# Sony_PS_Vita_USB-C.net
KiCad netlist of a schematic drawn in EAGLE
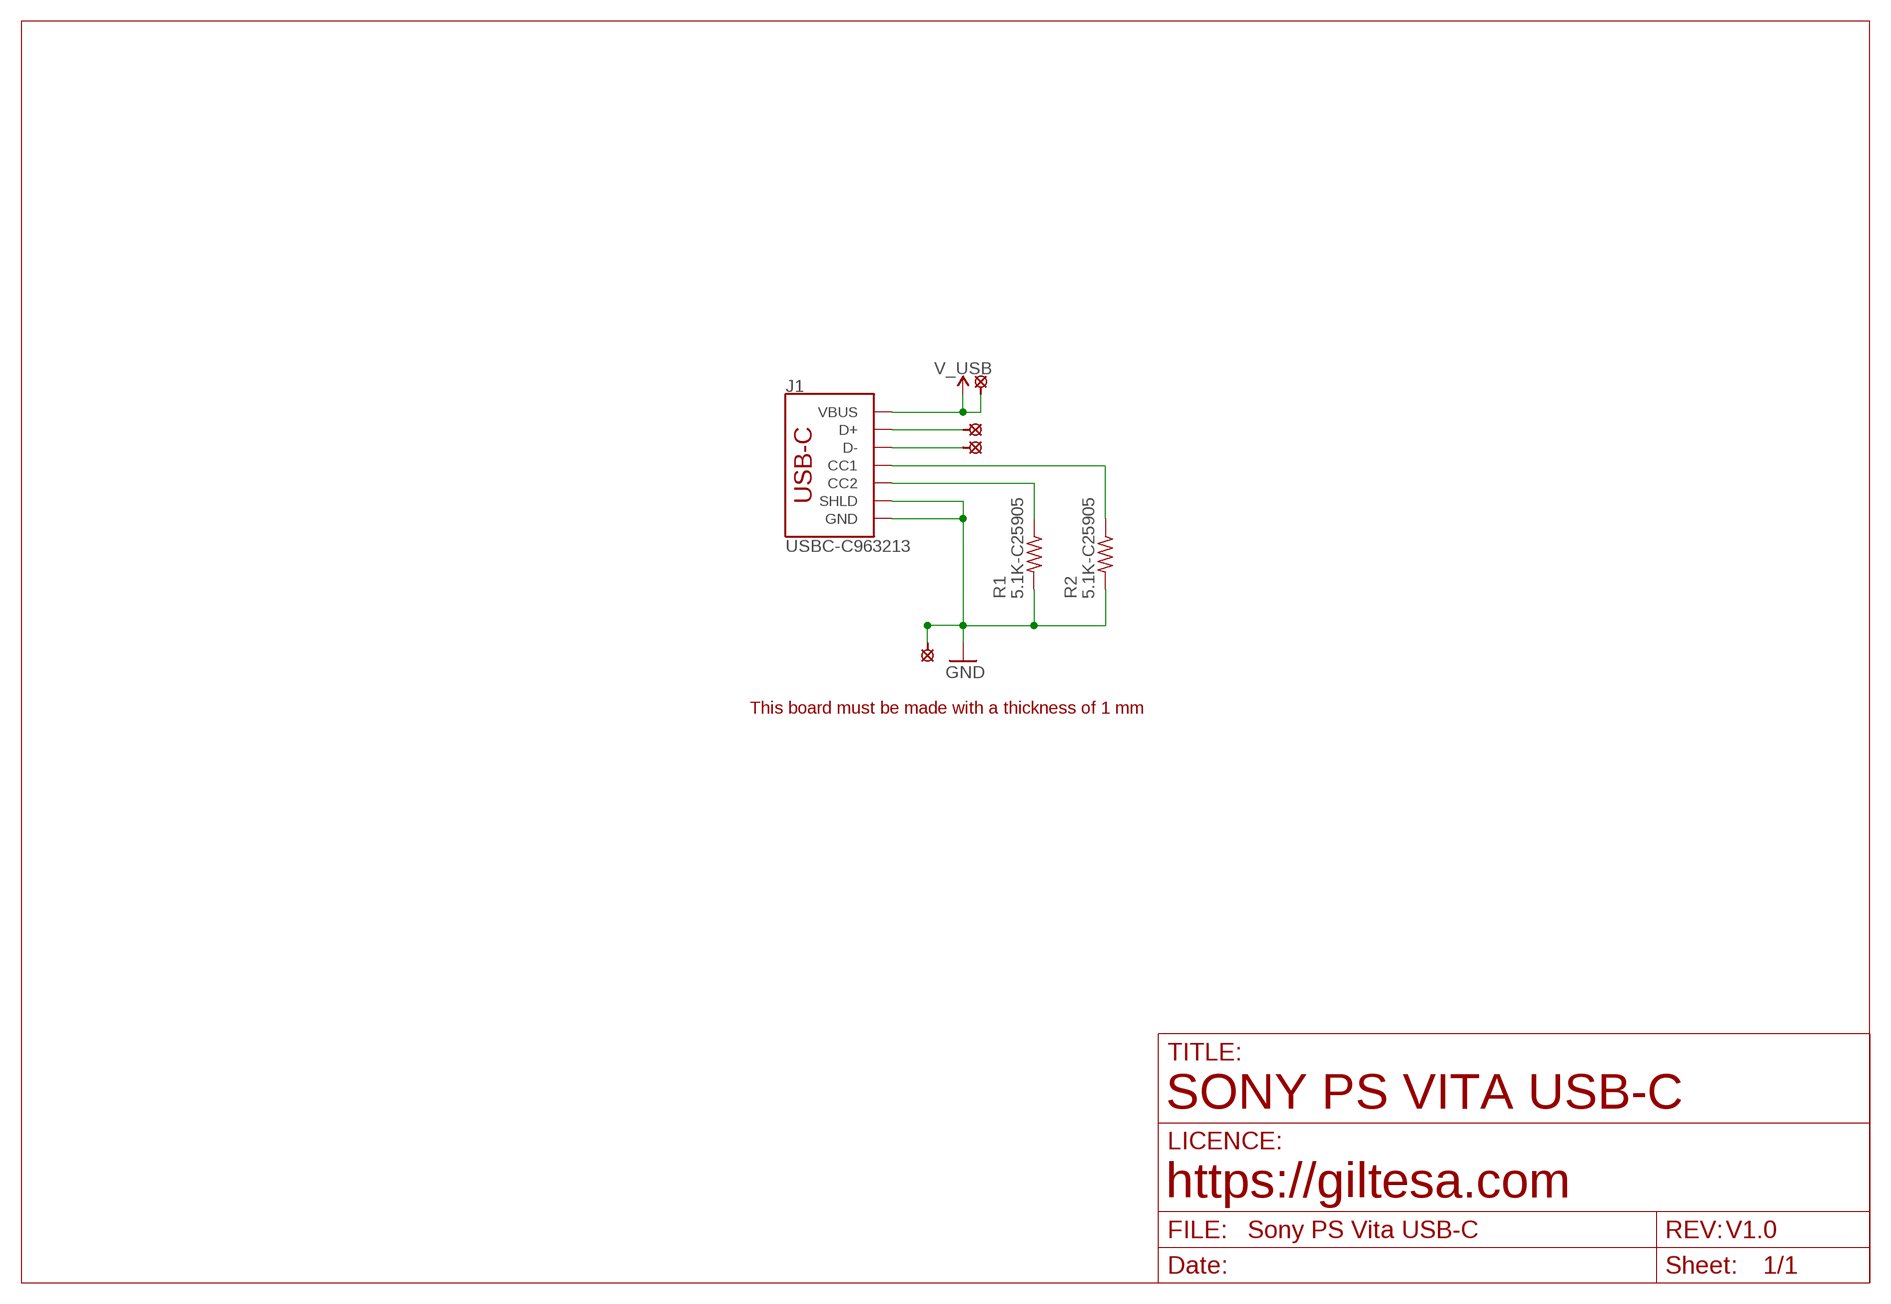
[diagram p0: schematic, sheet 1]

(export (version "E")
  (design (tool "Eeschema 10.0.6"))
  (components
    (comp (ref "J1")
      (value "USBC-C963213")
      (footprint "eagle-import:USB-C_18P_SLIM_GT-USB-7025")
      (libsource (lib "eagle-import") (part "USB-C_16P_DATA_SLIM"))
    )
    (comp (ref "R1")
      (value "5.1K-C25905")
      (footprint "eagle-import:R0402")
      (libsource (lib "eagle-import") (part "R0402"))
    )
    (comp (ref "R2")
      (value "5.1K-C25905")
      (footprint "eagle-import:R0402")
      (libsource (lib "eagle-import") (part "R0402"))
    )
    (comp (ref "U$3")
      (value "SOLDER_PAD-1.5")
      (footprint "eagle-import:SOLDER_PAD_1.5")
      (libsource (lib "eagle-import") (part "SOLDER_PAD-1.5"))
    )
    (comp (ref "U$4")
      (value "PAD_1.0")
      (footprint "eagle-import:PAD_1.0")
      (libsource (lib "eagle-import") (part "PAD_1.0"))
    )
    (comp (ref "U$5")
      (value "SOLDER_PAD-1.5")
      (footprint "eagle-import:SOLDER_PAD_1.5")
      (libsource (lib "eagle-import") (part "SOLDER_PAD-1.5"))
    )
    (comp (ref "U$6")
      (value "SOLDER_PAD-1.5")
      (footprint "eagle-import:SOLDER_PAD_1.5")
      (libsource (lib "eagle-import") (part "SOLDER_PAD-1.5"))
    )
    (comp (ref "U$7")
      (value "PAD_1.0")
      (footprint "eagle-import:PAD_1.0")
      (libsource (lib "eagle-import") (part "PAD_1.0"))
    )
    (comp (ref "U$8")
      (value "PAD_1.0")
      (footprint "eagle-import:PAD_1.0")
      (libsource (lib "eagle-import") (part "PAD_1.0"))
    )
    (comp (ref "U$9")
      (value "PAD_1.0")
      (footprint "eagle-import:PAD_1.0")
      (libsource (lib "eagle-import") (part "PAD_1.0"))
    )
  )
  (nets
    (net (code "1") (name "GND") (class "Default")
      (node (ref "J1") (pin "A1-GND") (pinfunction "GND_A1-GND") (pintype "bidirectional"))
      (node (ref "J1") (pin "A12-GND") (pinfunction "GND_A12-GND") (pintype "bidirectional"))
      (node (ref "J1") (pin "B1-GND") (pinfunction "GND_B1-GND") (pintype "bidirectional"))
      (node (ref "J1") (pin "B12-GND") (pinfunction "GND_B12-GND") (pintype "bidirectional"))
      (node (ref "J1") (pin "GND1") (pinfunction "GND_GND1") (pintype "bidirectional"))
      (node (ref "J1") (pin "GND2") (pinfunction "GND_GND2") (pintype "bidirectional"))
      (node (ref "J1") (pin "SHLD1") (pinfunction "SHLD_SHLD1") (pintype "bidirectional"))
      (node (ref "J1") (pin "SHLD2") (pinfunction "SHLD_SHLD2") (pintype "bidirectional"))
      (node (ref "J1") (pin "SHLD3") (pinfunction "SHLD_SHLD3") (pintype "bidirectional"))
      (node (ref "J1") (pin "SHLD4") (pinfunction "SHLD_SHLD4") (pintype "bidirectional"))
      (node (ref "R1") (pin "2") (pinfunction "2_2") (pintype "passive"))
      (node (ref "R2") (pin "2") (pinfunction "2_2") (pintype "passive"))
      (node (ref "U$4") (pin "P$1") (pinfunction "P$1_P$1") (pintype "bidirectional"))
      (node (ref "U$7") (pin "P$1") (pinfunction "P$1_P$1") (pintype "bidirectional"))
      (node (ref "U$8") (pin "P$1") (pinfunction "P$1_P$1") (pintype "bidirectional"))
      (node (ref "U$9") (pin "P$1") (pinfunction "P$1_P$1") (pintype "bidirectional"))
    )
    (net (code "2") (name "Net-(J1-CC1)") (class "Default")
      (node (ref "J1") (pin "A5-CC1") (pinfunction "CC1_A5-CC1") (pintype "bidirectional"))
      (node (ref "R2") (pin "1") (pinfunction "1_1") (pintype "passive"))
    )
    (net (code "3") (name "Net-(J1-CC2)") (class "Default")
      (node (ref "J1") (pin "B5-CC2") (pinfunction "CC2_B5-CC2") (pintype "bidirectional"))
      (node (ref "R1") (pin "1") (pinfunction "1_1") (pintype "passive"))
    )
    (net (code "4") (name "Net-(J1-D+-PadA6-DP1)") (class "Default")
      (node (ref "J1") (pin "A6-DP1") (pinfunction "D+_A6-DP1") (pintype "bidirectional"))
      (node (ref "J1") (pin "B6-DP2") (pinfunction "D+_B6-DP2") (pintype "bidirectional"))
      (node (ref "U$5") (pin "P$1") (pinfunction "P$1_P$1") (pintype "bidirectional"))
    )
    (net (code "5") (name "Net-(J1-D--PadA7-DN1)") (class "Default")
      (node (ref "J1") (pin "A7-DN1") (pinfunction "D-_A7-DN1") (pintype "bidirectional"))
      (node (ref "J1") (pin "B7-DN2") (pinfunction "D-_B7-DN2") (pintype "bidirectional"))
      (node (ref "U$6") (pin "P$1") (pinfunction "P$1_P$1") (pintype "bidirectional"))
    )
    (net (code "6") (name "V_USB") (class "Default")
      (node (ref "J1") (pin "A4-VBUS") (pinfunction "VBUS_A4-VBUS") (pintype "bidirectional"))
      (node (ref "J1") (pin "A9-VBUS") (pinfunction "VBUS_A9-VBUS") (pintype "bidirectional"))
      (node (ref "J1") (pin "B4-VBUS") (pinfunction "VBUS_B4-VBUS") (pintype "bidirectional"))
      (node (ref "J1") (pin "B9-VBUS") (pinfunction "VBUS_B9-VBUS") (pintype "bidirectional"))
      (node (ref "U$3") (pin "P$1") (pinfunction "P$1_P$1") (pintype "bidirectional"))
    )
  )
)
